# Dual6x09.net
KiCad netlist of a schematic drawn in EAGLE
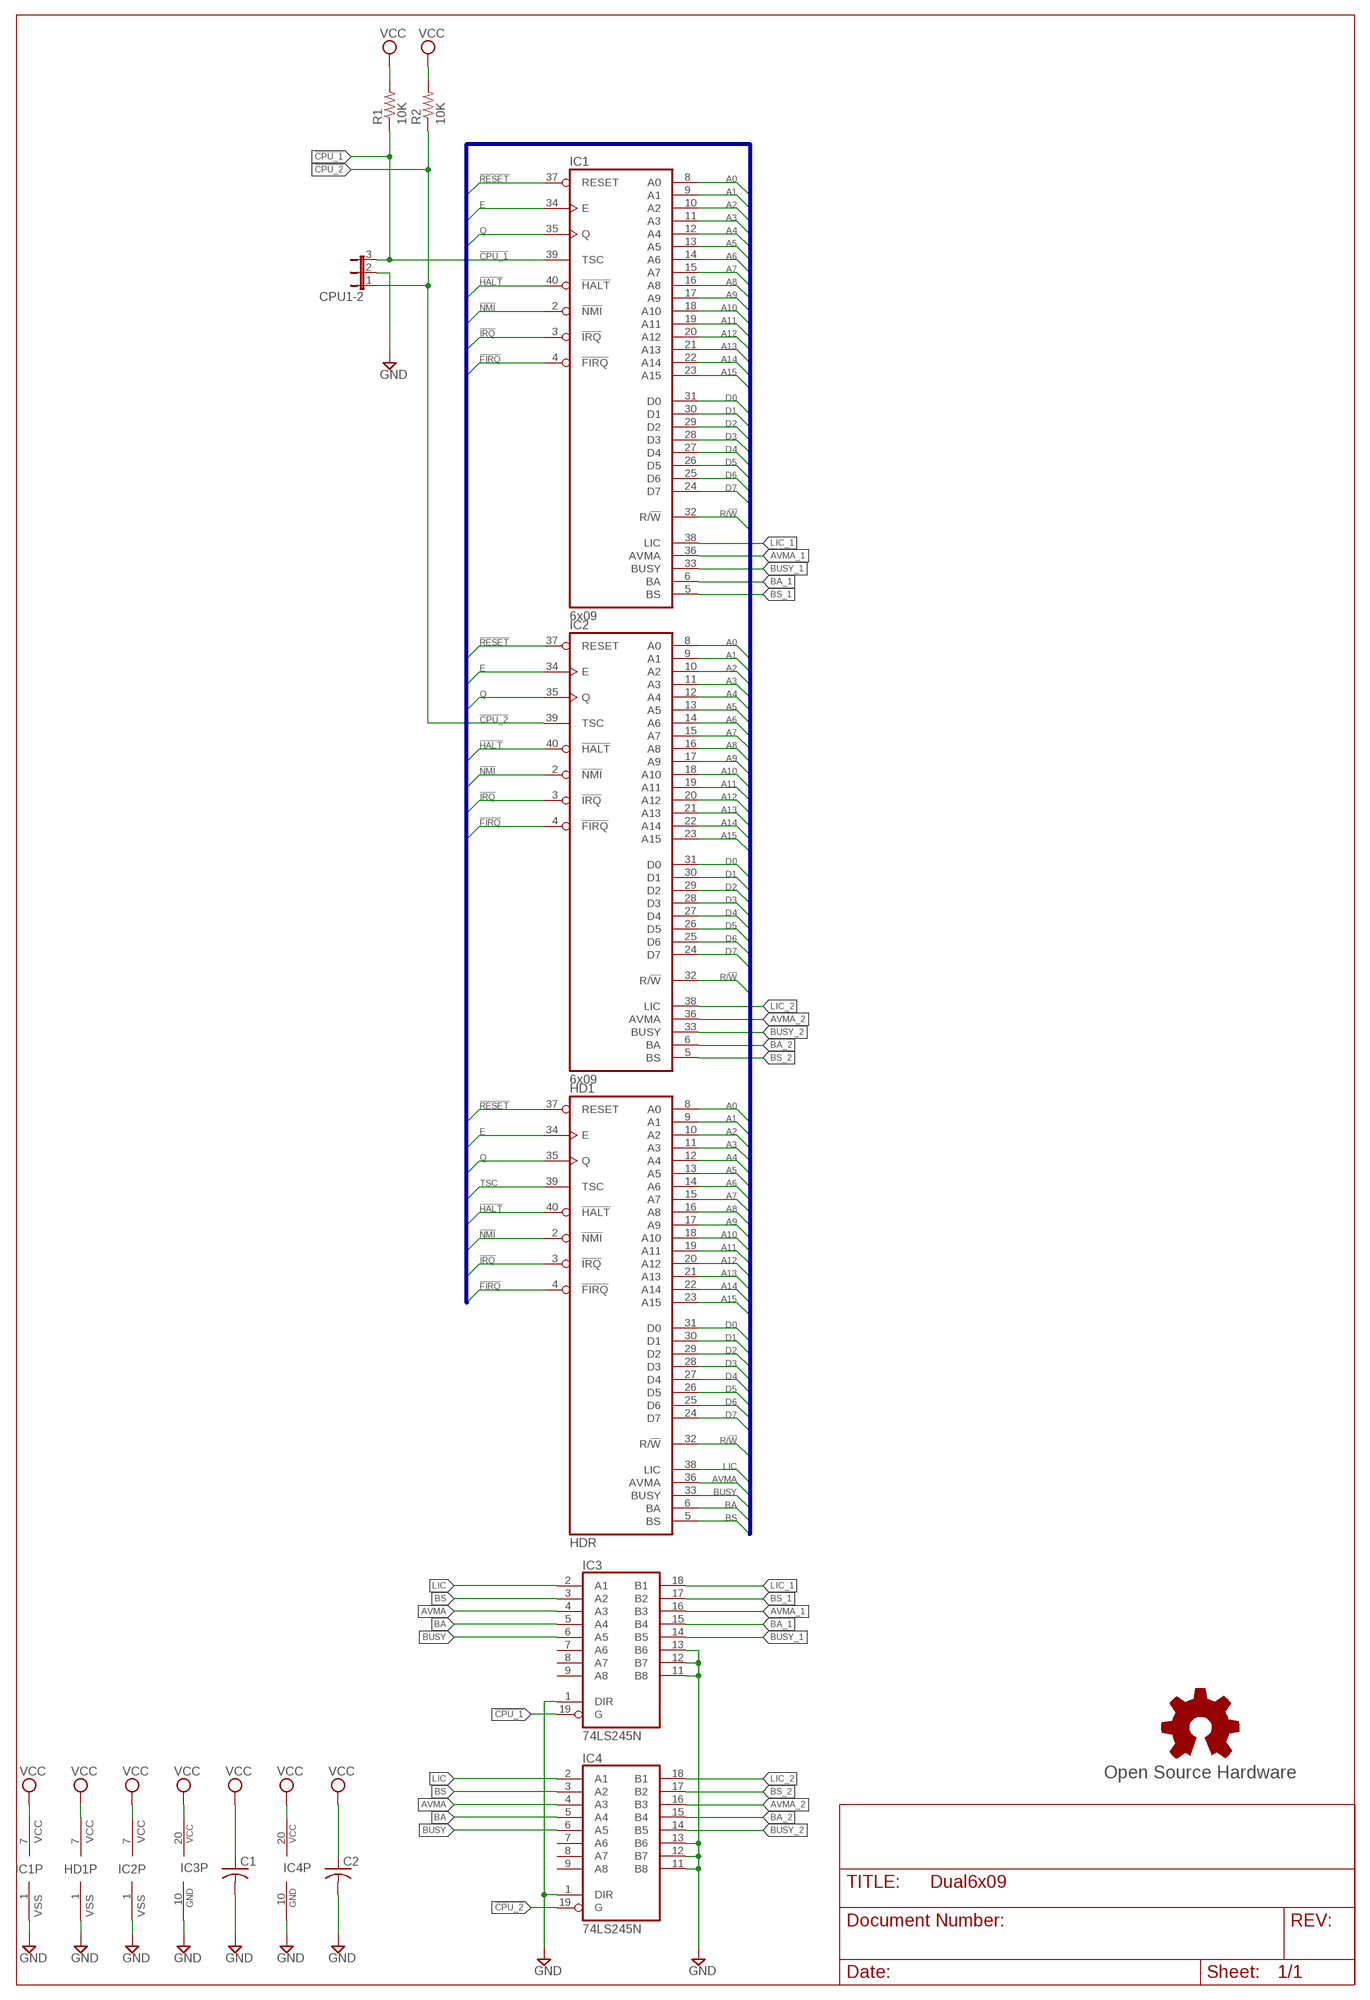
[diagram p0: schematic, sheet 1]

(export (version "E")
  (design (tool "Eeschema 10.0.6"))
  (components
    (comp (ref "C1")
      (value "C-US025-025X050")
      (footprint "eagle-import:C025-025X050")
      (libsource (lib "eagle-import") (part "C-US025-025X050"))
    )
    (comp (ref "C2")
      (value "C-US025-025X050")
      (footprint "eagle-import:C025-025X050")
      (libsource (lib "eagle-import") (part "C-US025-025X050"))
    )
    (comp (ref "CPU1-2")
      (value "JP2E")
      (footprint "eagle-import:JP2")
      (libsource (lib "eagle-import") (part "JP2E"))
    )
    (comp (ref "GOLD_ORB_SM1")
      (value "Open Source Hardware")
      (footprint "eagle-import:OSHW_5MM")
      (libsource (lib "eagle-import") (part "OSHWLOGOLOGO5MM"))
    )
    (comp (ref "HD1")
      (value "HDR")
      (footprint "eagle-import:DIL40-ROUNDPAD")
      (libsource (lib "eagle-import") (part "MC6809ER"))
    )
    (comp (ref "IC1")
      (value "6x09")
      (footprint "eagle-import:DIL40-ROUNDPAD")
      (libsource (lib "eagle-import") (part "MC6809ER"))
    )
    (comp (ref "IC2")
      (value "6x09")
      (footprint "eagle-import:DIL40-ROUNDPAD")
      (libsource (lib "eagle-import") (part "MC6809ER"))
    )
    (comp (ref "IC3")
      (value "74LS245N")
      (footprint "eagle-import:DIL20-RP")
      (libsource (lib "eagle-import") (part "74245NLS"))
    )
    (comp (ref "IC4")
      (value "74LS245N")
      (footprint "eagle-import:DIL20-RP")
      (libsource (lib "eagle-import") (part "74245NLS"))
    )
    (comp (ref "R1")
      (value "10K")
      (footprint "eagle-import:0204V")
      (libsource (lib "eagle-import") (part "R-US_0204/2V"))
    )
    (comp (ref "R2")
      (value "10K")
      (footprint "eagle-import:0204V")
      (libsource (lib "eagle-import") (part "R-US_0204/2V"))
    )
  )
  (nets
    (net (code "1") (name "/A0") (class "Default")
      (node (ref "HD1") (pin "8") (pinfunction "A0_8") (pintype "tri_state"))
      (node (ref "IC1") (pin "8") (pinfunction "A0_8") (pintype "tri_state"))
      (node (ref "IC2") (pin "8") (pinfunction "A0_8") (pintype "tri_state"))
    )
    (net (code "2") (name "/A1") (class "Default")
      (node (ref "HD1") (pin "9") (pinfunction "A1_9") (pintype "tri_state"))
      (node (ref "IC1") (pin "9") (pinfunction "A1_9") (pintype "tri_state"))
      (node (ref "IC2") (pin "9") (pinfunction "A1_9") (pintype "tri_state"))
    )
    (net (code "3") (name "/A2") (class "Default")
      (node (ref "HD1") (pin "10") (pinfunction "A2_10") (pintype "tri_state"))
      (node (ref "IC1") (pin "10") (pinfunction "A2_10") (pintype "tri_state"))
      (node (ref "IC2") (pin "10") (pinfunction "A2_10") (pintype "tri_state"))
    )
    (net (code "4") (name "/A3") (class "Default")
      (node (ref "HD1") (pin "11") (pinfunction "A3_11") (pintype "tri_state"))
      (node (ref "IC1") (pin "11") (pinfunction "A3_11") (pintype "tri_state"))
      (node (ref "IC2") (pin "11") (pinfunction "A3_11") (pintype "tri_state"))
    )
    (net (code "5") (name "/A4") (class "Default")
      (node (ref "HD1") (pin "12") (pinfunction "A4_12") (pintype "tri_state"))
      (node (ref "IC1") (pin "12") (pinfunction "A4_12") (pintype "tri_state"))
      (node (ref "IC2") (pin "12") (pinfunction "A4_12") (pintype "tri_state"))
    )
    (net (code "6") (name "/A5") (class "Default")
      (node (ref "HD1") (pin "13") (pinfunction "A5_13") (pintype "tri_state"))
      (node (ref "IC1") (pin "13") (pinfunction "A5_13") (pintype "tri_state"))
      (node (ref "IC2") (pin "13") (pinfunction "A5_13") (pintype "tri_state"))
    )
    (net (code "7") (name "/A6") (class "Default")
      (node (ref "HD1") (pin "14") (pinfunction "A6_14") (pintype "tri_state"))
      (node (ref "IC1") (pin "14") (pinfunction "A6_14") (pintype "tri_state"))
      (node (ref "IC2") (pin "14") (pinfunction "A6_14") (pintype "tri_state"))
    )
    (net (code "8") (name "/A7") (class "Default")
      (node (ref "HD1") (pin "15") (pinfunction "A7_15") (pintype "tri_state"))
      (node (ref "IC1") (pin "15") (pinfunction "A7_15") (pintype "tri_state"))
      (node (ref "IC2") (pin "15") (pinfunction "A7_15") (pintype "tri_state"))
    )
    (net (code "9") (name "/A8") (class "Default")
      (node (ref "HD1") (pin "16") (pinfunction "A8_16") (pintype "tri_state"))
      (node (ref "IC1") (pin "16") (pinfunction "A8_16") (pintype "tri_state"))
      (node (ref "IC2") (pin "16") (pinfunction "A8_16") (pintype "tri_state"))
    )
    (net (code "10") (name "/A9") (class "Default")
      (node (ref "HD1") (pin "17") (pinfunction "A9_17") (pintype "tri_state"))
      (node (ref "IC1") (pin "17") (pinfunction "A9_17") (pintype "tri_state"))
      (node (ref "IC2") (pin "17") (pinfunction "A9_17") (pintype "tri_state"))
    )
    (net (code "11") (name "/A10") (class "Default")
      (node (ref "HD1") (pin "18") (pinfunction "A10_18") (pintype "tri_state"))
      (node (ref "IC1") (pin "18") (pinfunction "A10_18") (pintype "tri_state"))
      (node (ref "IC2") (pin "18") (pinfunction "A10_18") (pintype "tri_state"))
    )
    (net (code "12") (name "/A11") (class "Default")
      (node (ref "HD1") (pin "19") (pinfunction "A11_19") (pintype "tri_state"))
      (node (ref "IC1") (pin "19") (pinfunction "A11_19") (pintype "tri_state"))
      (node (ref "IC2") (pin "19") (pinfunction "A11_19") (pintype "tri_state"))
    )
    (net (code "13") (name "/A12") (class "Default")
      (node (ref "HD1") (pin "20") (pinfunction "A12_20") (pintype "tri_state"))
      (node (ref "IC1") (pin "20") (pinfunction "A12_20") (pintype "tri_state"))
      (node (ref "IC2") (pin "20") (pinfunction "A12_20") (pintype "tri_state"))
    )
    (net (code "14") (name "/A13") (class "Default")
      (node (ref "HD1") (pin "21") (pinfunction "A13_21") (pintype "tri_state"))
      (node (ref "IC1") (pin "21") (pinfunction "A13_21") (pintype "tri_state"))
      (node (ref "IC2") (pin "21") (pinfunction "A13_21") (pintype "tri_state"))
    )
    (net (code "15") (name "/A14") (class "Default")
      (node (ref "HD1") (pin "22") (pinfunction "A14_22") (pintype "tri_state"))
      (node (ref "IC1") (pin "22") (pinfunction "A14_22") (pintype "tri_state"))
      (node (ref "IC2") (pin "22") (pinfunction "A14_22") (pintype "tri_state"))
    )
    (net (code "16") (name "/A15") (class "Default")
      (node (ref "HD1") (pin "23") (pinfunction "A15_23") (pintype "tri_state"))
      (node (ref "IC1") (pin "23") (pinfunction "A15_23") (pintype "tri_state"))
      (node (ref "IC2") (pin "23") (pinfunction "A15_23") (pintype "tri_state"))
    )
    (net (code "17") (name "/D0") (class "Default")
      (node (ref "HD1") (pin "31") (pinfunction "D0_31") (pintype "bidirectional"))
      (node (ref "IC1") (pin "31") (pinfunction "D0_31") (pintype "bidirectional"))
      (node (ref "IC2") (pin "31") (pinfunction "D0_31") (pintype "bidirectional"))
    )
    (net (code "18") (name "/D1") (class "Default")
      (node (ref "HD1") (pin "30") (pinfunction "D1_30") (pintype "bidirectional"))
      (node (ref "IC1") (pin "30") (pinfunction "D1_30") (pintype "bidirectional"))
      (node (ref "IC2") (pin "30") (pinfunction "D1_30") (pintype "bidirectional"))
    )
    (net (code "19") (name "/D2") (class "Default")
      (node (ref "HD1") (pin "29") (pinfunction "D2_29") (pintype "bidirectional"))
      (node (ref "IC1") (pin "29") (pinfunction "D2_29") (pintype "bidirectional"))
      (node (ref "IC2") (pin "29") (pinfunction "D2_29") (pintype "bidirectional"))
    )
    (net (code "20") (name "/D3") (class "Default")
      (node (ref "HD1") (pin "28") (pinfunction "D3_28") (pintype "bidirectional"))
      (node (ref "IC1") (pin "28") (pinfunction "D3_28") (pintype "bidirectional"))
      (node (ref "IC2") (pin "28") (pinfunction "D3_28") (pintype "bidirectional"))
    )
    (net (code "21") (name "/D4") (class "Default")
      (node (ref "HD1") (pin "27") (pinfunction "D4_27") (pintype "bidirectional"))
      (node (ref "IC1") (pin "27") (pinfunction "D4_27") (pintype "bidirectional"))
      (node (ref "IC2") (pin "27") (pinfunction "D4_27") (pintype "bidirectional"))
    )
    (net (code "22") (name "/D5") (class "Default")
      (node (ref "HD1") (pin "26") (pinfunction "D5_26") (pintype "bidirectional"))
      (node (ref "IC1") (pin "26") (pinfunction "D5_26") (pintype "bidirectional"))
      (node (ref "IC2") (pin "26") (pinfunction "D5_26") (pintype "bidirectional"))
    )
    (net (code "23") (name "/D6") (class "Default")
      (node (ref "HD1") (pin "25") (pinfunction "D6_25") (pintype "bidirectional"))
      (node (ref "IC1") (pin "25") (pinfunction "D6_25") (pintype "bidirectional"))
      (node (ref "IC2") (pin "25") (pinfunction "D6_25") (pintype "bidirectional"))
    )
    (net (code "24") (name "/D7") (class "Default")
      (node (ref "HD1") (pin "24") (pinfunction "D7_24") (pintype "bidirectional"))
      (node (ref "IC1") (pin "24") (pinfunction "D7_24") (pintype "bidirectional"))
      (node (ref "IC2") (pin "24") (pinfunction "D7_24") (pintype "bidirectional"))
    )
    (net (code "25") (name "/E") (class "Default")
      (node (ref "HD1") (pin "34") (pinfunction "E_34") (pintype "input"))
      (node (ref "IC1") (pin "34") (pinfunction "E_34") (pintype "input"))
      (node (ref "IC2") (pin "34") (pinfunction "E_34") (pintype "input"))
    )
    (net (code "26") (name "/Q") (class "Default")
      (node (ref "HD1") (pin "35") (pinfunction "Q_35") (pintype "input"))
      (node (ref "IC1") (pin "35") (pinfunction "Q_35") (pintype "input"))
      (node (ref "IC2") (pin "35") (pinfunction "Q_35") (pintype "input"))
    )
    (net (code "27") (name "/R{slash}~{W}") (class "Default")
      (node (ref "HD1") (pin "32") (pinfunction "R/~{W}_32") (pintype "output"))
      (node (ref "IC1") (pin "32") (pinfunction "R/~{W}_32") (pintype "output"))
      (node (ref "IC2") (pin "32") (pinfunction "R/~{W}_32") (pintype "output"))
    )
    (net (code "28") (name "/TSC") (class "Default")
      (node (ref "HD1") (pin "39") (pinfunction "TSC_39") (pintype "open_collector"))
    )
    (net (code "29") (name "/~{CPU_1}") (class "Default")
      (node (ref "CPU1-2") (pin "3") (pinfunction "3_3") (pintype "passive"))
      (node (ref "IC1") (pin "39") (pinfunction "TSC_39") (pintype "open_collector"))
      (node (ref "IC3") (pin "19") (pinfunction "G_19") (pintype "input"))
      (node (ref "R1") (pin "1") (pinfunction "1_1") (pintype "passive"))
    )
    (net (code "30") (name "/~{CPU_2}") (class "Default")
      (node (ref "CPU1-2") (pin "1") (pinfunction "1_1") (pintype "passive"))
      (node (ref "IC2") (pin "39") (pinfunction "TSC_39") (pintype "open_collector"))
      (node (ref "IC4") (pin "19") (pinfunction "G_19") (pintype "input"))
      (node (ref "R2") (pin "1") (pinfunction "1_1") (pintype "passive"))
    )
    (net (code "31") (name "/~{FIRQ}") (class "Default")
      (node (ref "HD1") (pin "4") (pinfunction "~{FIRQ}_4") (pintype "open_collector"))
      (node (ref "IC1") (pin "4") (pinfunction "~{FIRQ}_4") (pintype "open_collector"))
      (node (ref "IC2") (pin "4") (pinfunction "~{FIRQ}_4") (pintype "open_collector"))
    )
    (net (code "32") (name "/~{HALT}") (class "Default")
      (node (ref "HD1") (pin "40") (pinfunction "~{HALT}_40") (pintype "open_collector"))
      (node (ref "IC1") (pin "40") (pinfunction "~{HALT}_40") (pintype "open_collector"))
      (node (ref "IC2") (pin "40") (pinfunction "~{HALT}_40") (pintype "open_collector"))
    )
    (net (code "33") (name "/~{IRQ}") (class "Default")
      (node (ref "HD1") (pin "3") (pinfunction "~{IRQ}_3") (pintype "open_collector"))
      (node (ref "IC1") (pin "3") (pinfunction "~{IRQ}_3") (pintype "open_collector"))
      (node (ref "IC2") (pin "3") (pinfunction "~{IRQ}_3") (pintype "open_collector"))
    )
    (net (code "34") (name "/~{NMI}") (class "Default")
      (node (ref "HD1") (pin "2") (pinfunction "~{NMI}_2") (pintype "open_collector"))
      (node (ref "IC1") (pin "2") (pinfunction "~{NMI}_2") (pintype "open_collector"))
      (node (ref "IC2") (pin "2") (pinfunction "~{NMI}_2") (pintype "open_collector"))
    )
    (net (code "35") (name "/~{RESET}") (class "Default")
      (node (ref "HD1") (pin "37") (pinfunction "RESET_37") (pintype "input"))
      (node (ref "IC1") (pin "37") (pinfunction "RESET_37") (pintype "input"))
      (node (ref "IC2") (pin "37") (pinfunction "RESET_37") (pintype "input"))
    )
    (net (code "36") (name "AVMA") (class "Default")
      (node (ref "HD1") (pin "36") (pinfunction "AVMA_36") (pintype "output"))
      (node (ref "IC3") (pin "4") (pinfunction "A3_4") (pintype "bidirectional"))
      (node (ref "IC4") (pin "4") (pinfunction "A3_4") (pintype "bidirectional"))
    )
    (net (code "37") (name "AVMA_1") (class "Default")
      (node (ref "IC1") (pin "36") (pinfunction "AVMA_36") (pintype "output"))
      (node (ref "IC3") (pin "16") (pinfunction "B3_16") (pintype "bidirectional"))
    )
    (net (code "38") (name "AVMA_2") (class "Default")
      (node (ref "IC2") (pin "36") (pinfunction "AVMA_36") (pintype "output"))
      (node (ref "IC4") (pin "16") (pinfunction "B3_16") (pintype "bidirectional"))
    )
    (net (code "39") (name "BA") (class "Default")
      (node (ref "HD1") (pin "6") (pinfunction "BA_6") (pintype "output"))
      (node (ref "IC3") (pin "5") (pinfunction "A4_5") (pintype "bidirectional"))
      (node (ref "IC4") (pin "5") (pinfunction "A4_5") (pintype "bidirectional"))
    )
    (net (code "40") (name "BA_1") (class "Default")
      (node (ref "IC1") (pin "6") (pinfunction "BA_6") (pintype "output"))
      (node (ref "IC3") (pin "15") (pinfunction "B4_15") (pintype "bidirectional"))
    )
    (net (code "41") (name "BA_2") (class "Default")
      (node (ref "IC2") (pin "6") (pinfunction "BA_6") (pintype "output"))
      (node (ref "IC4") (pin "15") (pinfunction "B4_15") (pintype "bidirectional"))
    )
    (net (code "42") (name "BS") (class "Default")
      (node (ref "HD1") (pin "5") (pinfunction "BS_5") (pintype "output"))
      (node (ref "IC3") (pin "3") (pinfunction "A2_3") (pintype "bidirectional"))
      (node (ref "IC4") (pin "3") (pinfunction "A2_3") (pintype "bidirectional"))
    )
    (net (code "43") (name "BS_1") (class "Default")
      (node (ref "IC1") (pin "5") (pinfunction "BS_5") (pintype "output"))
      (node (ref "IC3") (pin "17") (pinfunction "B2_17") (pintype "bidirectional"))
    )
    (net (code "44") (name "BS_2") (class "Default")
      (node (ref "IC2") (pin "5") (pinfunction "BS_5") (pintype "output"))
      (node (ref "IC4") (pin "17") (pinfunction "B2_17") (pintype "bidirectional"))
    )
    (net (code "45") (name "BUSY") (class "Default")
      (node (ref "HD1") (pin "33") (pinfunction "BUSY_33") (pintype "output"))
      (node (ref "IC3") (pin "6") (pinfunction "A5_6") (pintype "bidirectional"))
      (node (ref "IC4") (pin "6") (pinfunction "A5_6") (pintype "bidirectional"))
    )
    (net (code "46") (name "BUSY_1") (class "Default")
      (node (ref "IC1") (pin "33") (pinfunction "BUSY_33") (pintype "output"))
      (node (ref "IC3") (pin "14") (pinfunction "B5_14") (pintype "bidirectional"))
    )
    (net (code "47") (name "BUSY_2") (class "Default")
      (node (ref "IC2") (pin "33") (pinfunction "BUSY_33") (pintype "output"))
      (node (ref "IC4") (pin "14") (pinfunction "B5_14") (pintype "bidirectional"))
    )
    (net (code "48") (name "GND") (class "Default")
      (node (ref "C1") (pin "2") (pinfunction "2_2") (pintype "passive"))
      (node (ref "C2") (pin "2") (pinfunction "2_2") (pintype "passive"))
      (node (ref "CPU1-2") (pin "2") (pinfunction "2_2") (pintype "passive"))
      (node (ref "HD1") (pin "1") (pinfunction "VSS_1") (pintype "power_in"))
      (node (ref "IC1") (pin "1") (pinfunction "VSS_1") (pintype "power_in"))
      (node (ref "IC2") (pin "1") (pinfunction "VSS_1") (pintype "power_in"))
      (node (ref "IC3") (pin "1") (pinfunction "DIR_1") (pintype "input"))
      (node (ref "IC3") (pin "10") (pinfunction "GND_10") (pintype "power_in"))
      (node (ref "IC3") (pin "11") (pinfunction "B8_11") (pintype "bidirectional"))
      (node (ref "IC3") (pin "12") (pinfunction "B7_12") (pintype "bidirectional"))
      (node (ref "IC3") (pin "13") (pinfunction "B6_13") (pintype "bidirectional"))
      (node (ref "IC4") (pin "1") (pinfunction "DIR_1") (pintype "input"))
      (node (ref "IC4") (pin "10") (pinfunction "GND_10") (pintype "power_in"))
      (node (ref "IC4") (pin "11") (pinfunction "B8_11") (pintype "bidirectional"))
      (node (ref "IC4") (pin "12") (pinfunction "B7_12") (pintype "bidirectional"))
      (node (ref "IC4") (pin "13") (pinfunction "B6_13") (pintype "bidirectional"))
    )
    (net (code "49") (name "LIC") (class "Default")
      (node (ref "HD1") (pin "38") (pinfunction "LIC_38") (pintype "output"))
      (node (ref "IC3") (pin "2") (pinfunction "A1_2") (pintype "bidirectional"))
      (node (ref "IC4") (pin "2") (pinfunction "A1_2") (pintype "bidirectional"))
    )
    (net (code "50") (name "LIC_1") (class "Default")
      (node (ref "IC1") (pin "38") (pinfunction "LIC_38") (pintype "output"))
      (node (ref "IC3") (pin "18") (pinfunction "B1_18") (pintype "bidirectional"))
    )
    (net (code "51") (name "LIC_2") (class "Default")
      (node (ref "IC2") (pin "38") (pinfunction "LIC_38") (pintype "output"))
      (node (ref "IC4") (pin "18") (pinfunction "B1_18") (pintype "bidirectional"))
    )
    (net (code "52") (name "VCC") (class "Default")
      (node (ref "C1") (pin "1") (pinfunction "1_1") (pintype "passive"))
      (node (ref "C2") (pin "1") (pinfunction "1_1") (pintype "passive"))
      (node (ref "HD1") (pin "7") (pinfunction "VCC_7") (pintype "power_in"))
      (node (ref "IC1") (pin "7") (pinfunction "VCC_7") (pintype "power_in"))
      (node (ref "IC2") (pin "7") (pinfunction "VCC_7") (pintype "power_in"))
      (node (ref "IC3") (pin "20") (pinfunction "VCC_20") (pintype "power_in"))
      (node (ref "IC4") (pin "20") (pinfunction "VCC_20") (pintype "power_in"))
      (node (ref "R1") (pin "2") (pinfunction "2_2") (pintype "passive"))
      (node (ref "R2") (pin "2") (pinfunction "2_2") (pintype "passive"))
    )
    (net (code "53") (name "unconnected-(IC3A-A6-Pad7)") (class "Default")
      (node (ref "IC3") (pin "7") (pinfunction "A6_7") (pintype "bidirectional"))
    )
    (net (code "54") (name "unconnected-(IC3A-A7-Pad8)") (class "Default")
      (node (ref "IC3") (pin "8") (pinfunction "A7_8") (pintype "bidirectional"))
    )
    (net (code "55") (name "unconnected-(IC3A-A8-Pad9)") (class "Default")
      (node (ref "IC3") (pin "9") (pinfunction "A8_9") (pintype "bidirectional"))
    )
    (net (code "56") (name "unconnected-(IC4A-A6-Pad7)") (class "Default")
      (node (ref "IC4") (pin "7") (pinfunction "A6_7") (pintype "bidirectional"))
    )
    (net (code "57") (name "unconnected-(IC4A-A7-Pad8)") (class "Default")
      (node (ref "IC4") (pin "8") (pinfunction "A7_8") (pintype "bidirectional"))
    )
    (net (code "58") (name "unconnected-(IC4A-A8-Pad9)") (class "Default")
      (node (ref "IC4") (pin "9") (pinfunction "A8_9") (pintype "bidirectional"))
    )
  )
)
